# VT_8S_LHS_Bot_V0_1.net
KiCad netlist of a schematic drawn in Altium Designer
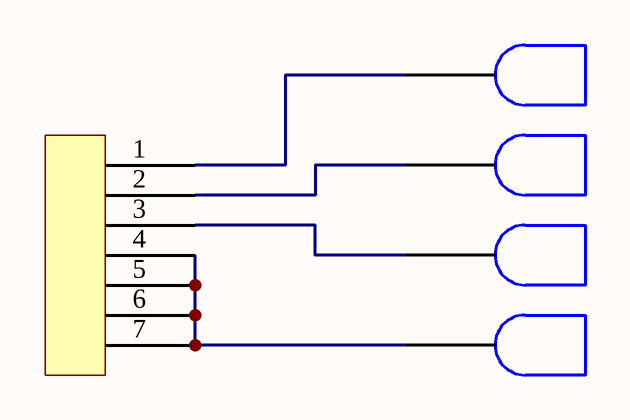
[diagram p0: VT 8S LHS Bot V0.1.SchDoc]

(export (version "E")
  (design (tool "Eeschema 10.0.6"))
  (components
    (comp (ref "J7")
      (value "Voltage Tap")
      (footprint "Voltage Tap")
      (libsource (lib "Voltage Taps V0.1") (part "Voltage Tap"))
    )
    (comp (ref "J8")
      (value "Voltage Tap")
      (footprint "Voltage Tap")
      (libsource (lib "Voltage Taps V0.1") (part "Voltage Tap"))
    )
    (comp (ref "J9")
      (value "Voltage Tap")
      (footprint "Voltage Tap")
      (libsource (lib "Voltage Taps V0.1") (part "Voltage Tap"))
    )
    (comp (ref "J10")
      (value "84953-7-FPC")
      (footprint "84953-7 - FPC")
      (description "FPC Connectors, Flex-to-Board, 7 Position, .039 in [1 mm] Centerline, FPC Side Connector")
      (libsource (lib "TE_Con") (part "84953-7-FPC"))
    )
    (comp (ref "J11")
      (value "Voltage Tap")
      (footprint "Voltage Tap")
      (libsource (lib "Voltage Taps V0.1") (part "Voltage Tap"))
    )
  )
  (nets
    (net (code "1") (name "Net-(J10-Pad1)") (class "Default")
      (node (ref "J10") (pin "1") (pintype "passive"))
      (node (ref "J7") (pin "1") (pintype "passive"))
    )
    (net (code "2") (name "Net-(J10-Pad2)") (class "Default")
      (node (ref "J10") (pin "2") (pintype "passive"))
      (node (ref "J8") (pin "1") (pintype "passive"))
    )
    (net (code "3") (name "Net-(J10-Pad3)") (class "Default")
      (node (ref "J10") (pin "3") (pintype "passive"))
      (node (ref "J9") (pin "1") (pintype "passive"))
    )
    (net (code "4") (name "Net-(J10-Pad4)") (class "Default")
      (node (ref "J10") (pin "4") (pintype "passive"))
      (node (ref "J10") (pin "5") (pintype "passive"))
      (node (ref "J10") (pin "6") (pintype "passive"))
      (node (ref "J10") (pin "7") (pintype "passive"))
      (node (ref "J11") (pin "1") (pintype "passive"))
    )
  )
)
